# System_Supply.net
KiCad netlist of a schematic drawn in Altium Designer
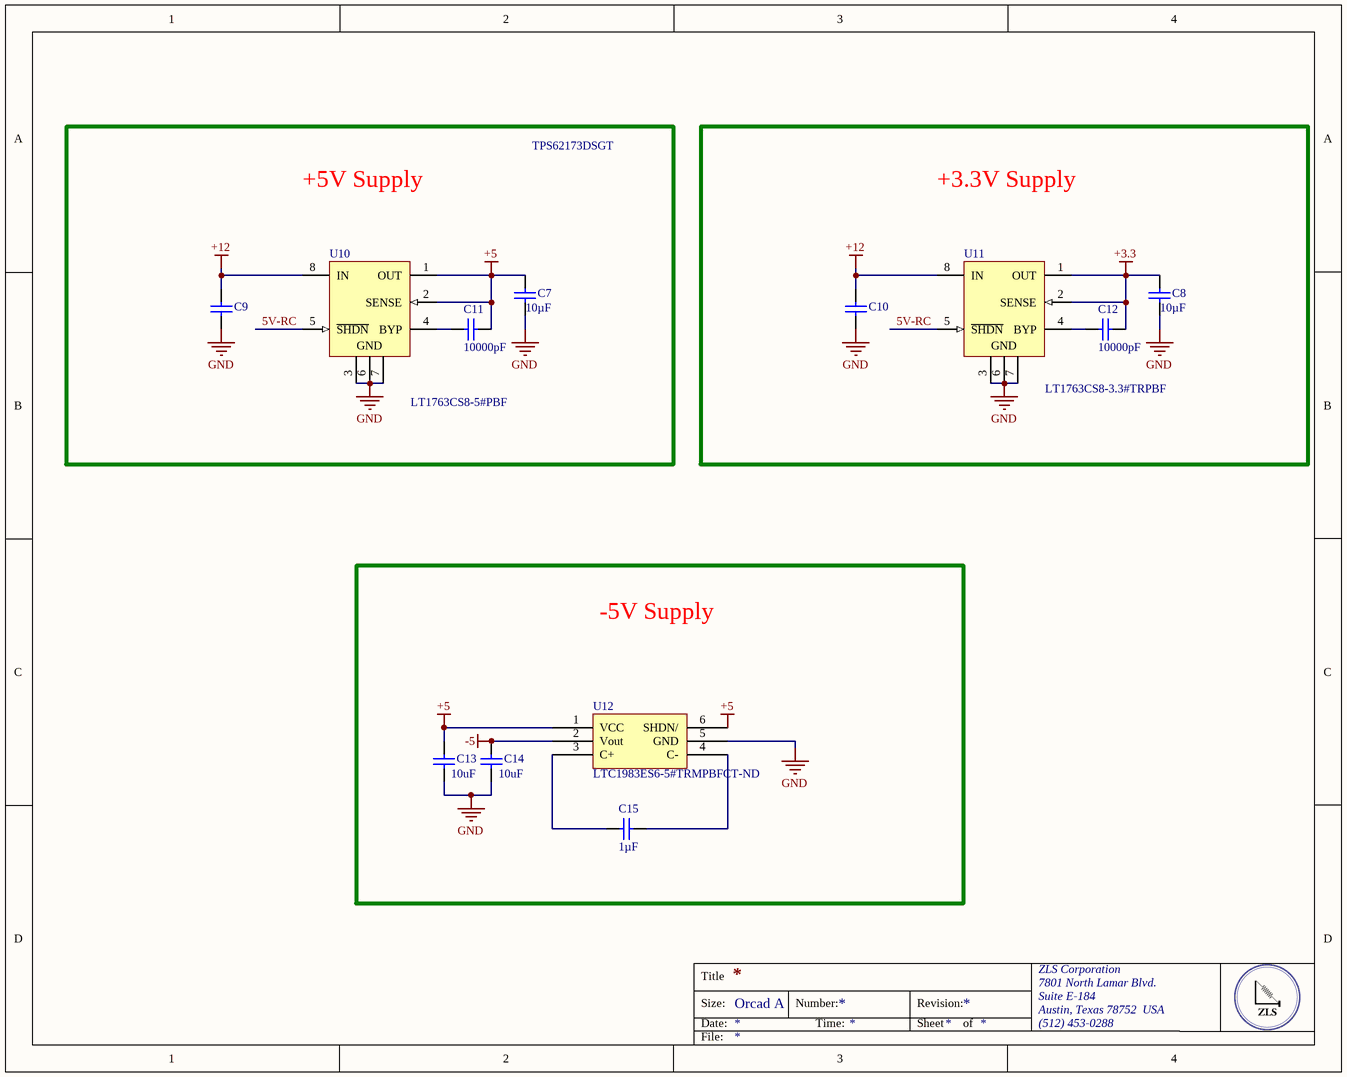
[diagram p0: System_Supply.SchDoc]

(export (version "E")
  (design (tool "Eeschema 10.0.6"))
  (components
    (comp (ref "C7")
      (value "CAP CER 1UF 50V X7R 1210")
      (footprint "CAPC1206(3216)130_N")
      (fields
        (field (name "MANUFACTURER") "Murata Electronics North America")
        (field (name "MANUFACTURER PART NUMBER") "GRM32RR71H105KA01L")
        (field (name "CAPACITANCE") "10µF")
        (field (name "TOLERANCE") "±10%")
      )
      (libsource (lib "Altium Content Vault") (part "CMP-1037-04913-1"))
    )
    (comp (ref "C8")
      (value "CAP CER 1UF 50V X7R 1210")
      (footprint "CAPC1206(3216)130_N")
      (fields
        (field (name "MANUFACTURER") "Murata Electronics North America")
        (field (name "MANUFACTURER PART NUMBER") "GRM32RR71H105KA01L")
        (field (name "CAPACITANCE") "10µF")
        (field (name "TOLERANCE") "±10%")
      )
      (libsource (lib "Altium Content Vault") (part "CMP-1037-04913-1"))
    )
    (comp (ref "C9")
      (value "1uF")
      (footprint "CAPC1206(3216)130_N")
      (libsource (lib "Altium Content Vault") (part "CMP-1037-04913-1"))
    )
    (comp (ref "C10")
      (value "1uF")
      (footprint "CAPC1206(3216)130_N")
      (libsource (lib "Altium Content Vault") (part "CMP-1037-04913-1"))
    )
    (comp (ref "C11")
      (value "CAP CER 1UF 50V X7R 1210")
      (footprint "CAPC1206(3216)130_N")
      (fields
        (field (name "MANUFACTURER") "Murata Electronics North America")
        (field (name "MANUFACTURER PART NUMBER") "GRM32RR71H105KA01L")
        (field (name "CAPACITANCE") "10000pF")
        (field (name "TOLERANCE") "±10%")
      )
      (libsource (lib "Altium Content Vault") (part "CMP-1037-04913-1"))
    )
    (comp (ref "C12")
      (value "CAP CER 1UF 50V X7R 1210")
      (footprint "CAPC1206(3216)130_N")
      (fields
        (field (name "MANUFACTURER") "Murata Electronics North America")
        (field (name "MANUFACTURER PART NUMBER") "GRM32RR71H105KA01L")
        (field (name "CAPACITANCE") "10000pF")
        (field (name "TOLERANCE") "±10%")
      )
      (libsource (lib "Altium Content Vault") (part "CMP-1037-04913-1"))
    )
    (comp (ref "C13")
      (value "CAP CER 10UF 6.3V X5R 1206")
      (footprint "CAPC1206(3216)130_N")
      (fields
        (field (name "MANUFACTURER") "Taiyo Yuden")
        (field (name "MANUFACTURER PART NUMBER") "JMK316BJ106ML-T")
        (field (name "TOLERANCE") "±20%")
        (field (name "CAPACITANCE") "10uF")
      )
      (libsource (lib "Altium Content Vault") (part "CMP-1037-04913-1"))
    )
    (comp (ref "C14")
      (value "CAP CER 10UF 6.3V X5R 1206")
      (footprint "CAPC1206(3216)130_N")
      (fields
        (field (name "MANUFACTURER") "Taiyo Yuden")
        (field (name "MANUFACTURER PART NUMBER") "JMK316BJ106ML-T")
        (field (name "TOLERANCE") "±20%")
        (field (name "CAPACITANCE") "10uF")
      )
      (libsource (lib "Altium Content Vault") (part "CMP-1037-04913-1"))
    )
    (comp (ref "C15")
      (value "CAP CER 1UF 10V X5R 0805")
      (footprint "CAPC1206(3216)130_N")
      (fields
        (field (name "CAPACITANCE") "1µF")
        (field (name "MANUFACTURER") "Taiyo Yuden")
        (field (name "MANUFACTURER PART NUMBER") "LMK212BJ105MD-T")
        (field (name "TOLERANCE") "±20%")
      )
      (libsource (lib "Altium Content Vault") (part "CMP-1037-04913-1"))
    )
    (comp (ref "U10")
      (value "LT1763CS8-5#PBF")
      (footprint "LT-S8-8_M")
      (fields (field (name "MANUFACTURER") "Linear Technology"))
      (libsource (lib "Altium Content Vault") (part "LT-LT1763-S8-8"))
    )
    (comp (ref "U11")
      (value "LT1763CS8-3.3#TRPBF")
      (footprint "LT-S8-8_N")
      (fields (field (name "MANUFACTURER") "Linear Technology"))
      (libsource (lib "Altium Content Vault") (part "LT-LT1763-S8-8"))
    )
    (comp (ref "U12")
      (value "LTC1983ES6-5#TRMPBF")
      (footprint "SOT95P323X100-6N")
      (fields
        (field (name "SUPPLIER PART NUMBER 1") "LTC1983ES6-5#TRMPBFCT-ND")
        (field (name "MANUFACTURER") "Linear Technology/Analog Devices")
        (field (name "BASE PART NUMBER") "LTC1983-5")
      )
      (libsource (lib "ZLS_Schematic_lib") (part "LTC1983ES6-5#TRMPBF"))
    )
  )
  (nets
    (net (code "1") (name "+3.3") (class "Default")
      (node (ref "C12") (pin "1") (pinfunction "1_1") (pintype "passive"))
      (node (ref "C8") (pin "2") (pinfunction "2_2") (pintype "passive"))
      (node (ref "U11") (pin "1") (pinfunction "OUT_1") (pintype "power_in"))
      (node (ref "U11") (pin "2") (pinfunction "SENSE_2") (pintype "input"))
    )
    (net (code "2") (name "+5") (class "Default")
      (node (ref "C11") (pin "1") (pinfunction "1_1") (pintype "passive"))
      (node (ref "C13") (pin "2") (pinfunction "2_2") (pintype "passive"))
      (node (ref "C7") (pin "2") (pinfunction "2_2") (pintype "passive"))
      (node (ref "U10") (pin "1") (pinfunction "OUT_1") (pintype "power_in"))
      (node (ref "U10") (pin "2") (pinfunction "SENSE_2") (pintype "input"))
      (node (ref "U12") (pin "1") (pinfunction "VCC_1") (pintype "passive"))
      (node (ref "U12") (pin "6") (pinfunction "SHDN/_6") (pintype "passive"))
    )
    (net (code "3") (name "+12") (class "Default")
      (node (ref "C10") (pin "2") (pinfunction "2_2") (pintype "passive"))
      (node (ref "C9") (pin "2") (pinfunction "2_2") (pintype "passive"))
      (node (ref "U10") (pin "8") (pinfunction "IN_8") (pintype "power_in"))
      (node (ref "U11") (pin "8") (pinfunction "IN_8") (pintype "power_in"))
    )
    (net (code "4") (name "-5") (class "Default")
      (node (ref "C14") (pin "2") (pinfunction "2_2") (pintype "passive"))
      (node (ref "U12") (pin "2") (pinfunction "Vout_2") (pintype "passive"))
    )
    (net (code "5") (name "/5V-RC") (class "Default")
      (node (ref "U10") (pin "5") (pinfunction "~{SHDN}_5") (pintype "input"))
      (node (ref "U11") (pin "5") (pinfunction "~{SHDN}_5") (pintype "input"))
    )
    (net (code "6") (name "GND") (class "Default")
      (node (ref "C10") (pin "1") (pinfunction "1_1") (pintype "passive"))
      (node (ref "C13") (pin "1") (pinfunction "1_1") (pintype "passive"))
      (node (ref "C14") (pin "1") (pinfunction "1_1") (pintype "passive"))
      (node (ref "C7") (pin "1") (pinfunction "1_1") (pintype "passive"))
      (node (ref "C8") (pin "1") (pinfunction "1_1") (pintype "passive"))
      (node (ref "C9") (pin "1") (pinfunction "1_1") (pintype "passive"))
      (node (ref "U10") (pin "3") (pinfunction "GND_3") (pintype "power_in"))
      (node (ref "U10") (pin "6") (pinfunction "GND_6") (pintype "power_in"))
      (node (ref "U10") (pin "7") (pinfunction "GND_7") (pintype "power_in"))
      (node (ref "U11") (pin "3") (pinfunction "GND_3") (pintype "power_in"))
      (node (ref "U11") (pin "6") (pinfunction "GND_6") (pintype "power_in"))
      (node (ref "U11") (pin "7") (pinfunction "GND_7") (pintype "power_in"))
      (node (ref "U12") (pin "5") (pinfunction "GND_5") (pintype "passive"))
    )
    (net (code "7") (name "Net-(U10-BYP)") (class "Default")
      (node (ref "C11") (pin "2") (pinfunction "2_2") (pintype "passive"))
      (node (ref "U10") (pin "4") (pinfunction "BYP_4") (pintype "passive"))
    )
    (net (code "8") (name "Net-(U11-BYP)") (class "Default")
      (node (ref "C12") (pin "2") (pinfunction "2_2") (pintype "passive"))
      (node (ref "U11") (pin "4") (pinfunction "BYP_4") (pintype "passive"))
    )
    (net (code "9") (name "Net-(U12-C+)") (class "Default")
      (node (ref "C15") (pin "2") (pinfunction "2_2") (pintype "passive"))
      (node (ref "U12") (pin "3") (pinfunction "C+_3") (pintype "passive"))
    )
    (net (code "10") (name "Net-(U12-C-)") (class "Default")
      (node (ref "C15") (pin "1") (pinfunction "1_1") (pintype "passive"))
      (node (ref "U12") (pin "4") (pinfunction "C-_4") (pintype "passive"))
    )
  )
)
